# Sheet1.net
KiCad netlist of a schematic drawn in Altium Designer
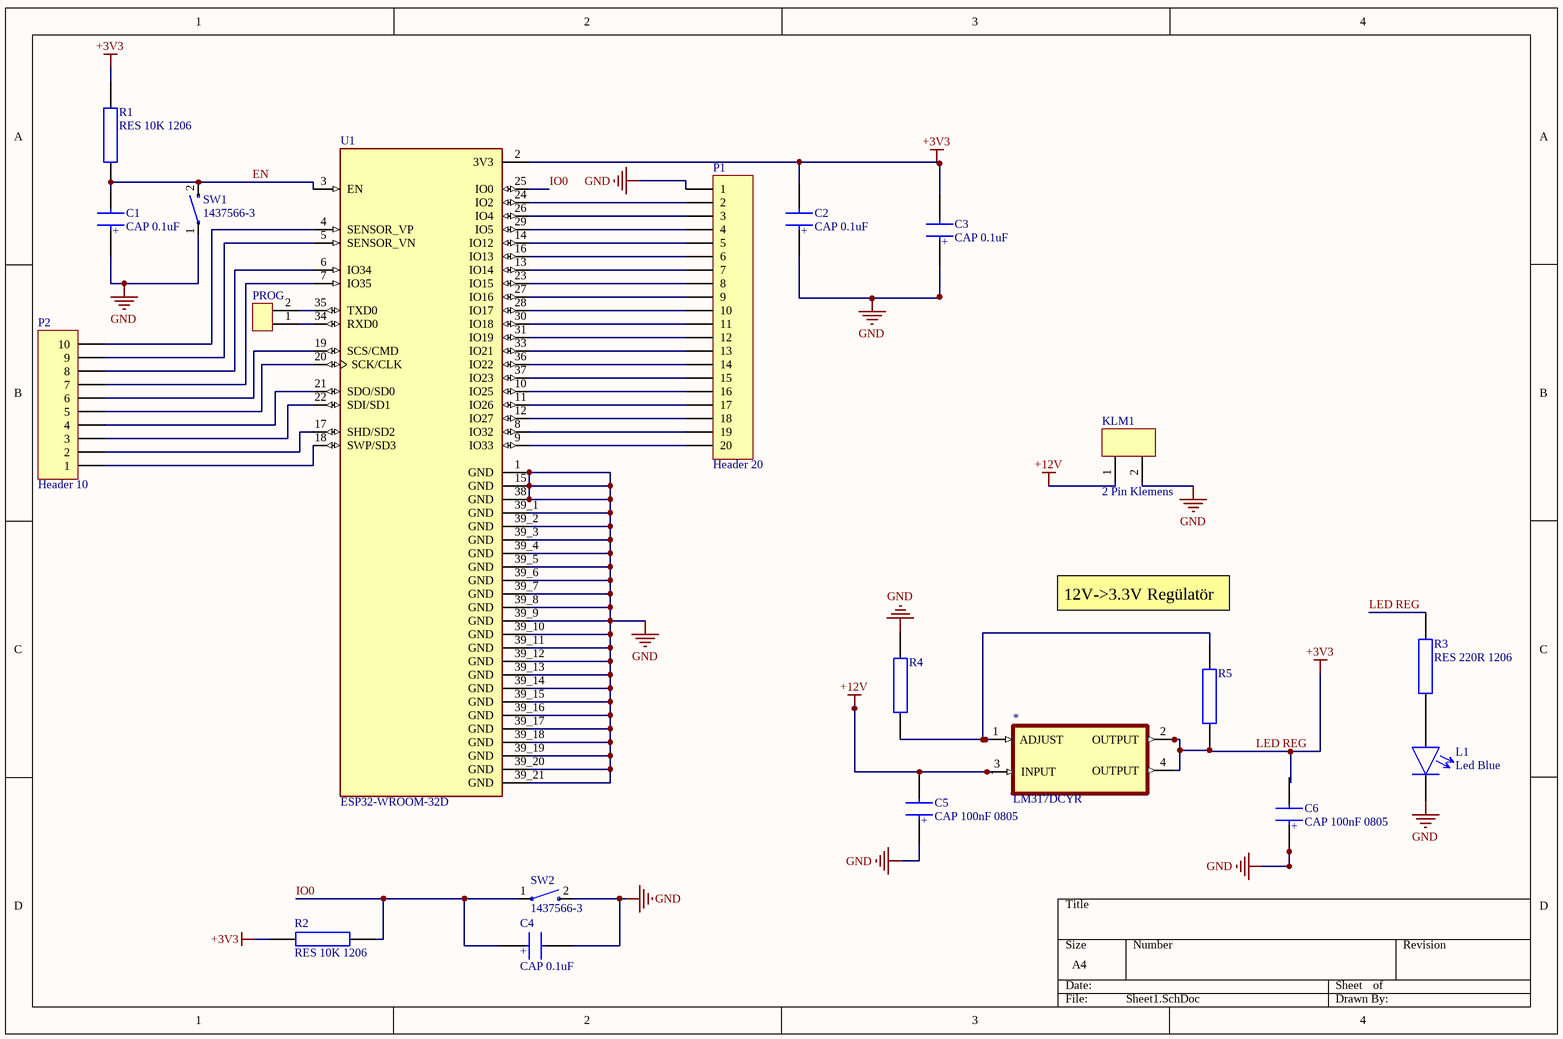
[diagram p0: Sheet1.SchDoc]

(export (version "E")
  (design (tool "Eeschema 10.0.6"))
  (components
    (comp (ref "*")
      (value "LM317DCYR")
      (footprint "SOT230P700X180-4N")
      (libsource (lib "Schlib") (part "LM317DCYR"))
    )
    (comp (ref "C1")
      (value "CAP 0.1uF")
      (footprint "CAP_805")
      (description "0805 smd")
      (libsource (lib "Udemy_Schlib1") (part "CAP 1uF"))
    )
    (comp (ref "C2")
      (value "CAP 0.1uF")
      (footprint "CAP_805")
      (description "0805 smd")
      (libsource (lib "Udemy_Schlib1") (part "CAP 1uF"))
    )
    (comp (ref "C3")
      (value "CAP 0.1uF")
      (footprint "CAP_805")
      (description "0805 smd")
      (libsource (lib "Udemy_Schlib1") (part "CAP 1uF"))
    )
    (comp (ref "C4")
      (value "CAP 0.1uF")
      (footprint "CAP_805")
      (description "0805 smd")
      (libsource (lib "Udemy_Schlib1") (part "CAP 1uF"))
    )
    (comp (ref "C5")
      (value "CAP 100nF 0805")
      (footprint "CAP_805")
      (description "0805 smd")
      (libsource (lib "Udemy_Schlib1") (part "CAP 100nF 0805"))
    )
    (comp (ref "C6")
      (value "CAP 100nF 0805")
      (footprint "CAP_805")
      (description "0805 smd")
      (libsource (lib "Udemy_Schlib1") (part "CAP 100nF 0805"))
    )
    (comp (ref "KLM1")
      (value "2 Pin Klemens")
      (footprint "5.08mm-2 pin")
      (description "5.08mm 2 pin klemens")
      (libsource (lib "Udemy_Schlib1") (part "2 Pin Klemens"))
    )
    (comp (ref "L1")
      (value "Led Blue")
      (footprint "Led 1206")
      (libsource (lib "Udemy_Schlib1") (part "Led Blue"))
    )
    (comp (ref "P1")
      (value "Header 20")
      (footprint "HDR1X20")
      (description "Header, 20-Pin")
      (fields (field (name "PUBLISHER") "Altium Limited"))
      (libsource (lib "Miscellaneous Connectors") (part "Header 20"))
    )
    (comp (ref "P2")
      (value "Header 10")
      (footprint "HDR1X10")
      (description "Header, 10-Pin")
      (fields (field (name "PUBLISHER") "Altium Limited"))
      (libsource (lib "Miscellaneous Connectors") (part "Header 10"))
    )
    (comp (ref "PROG")
      (value "2 Pin Jst Konnektör")
      (footprint "2 pin konnektor")
      (description "2.50 mm 2 pin jst")
      (libsource (lib "Udemy_Schlib1") (part "2 Pin Jst Konnektör"))
    )
    (comp (ref "R1")
      (value "RES 10K 1206")
      (footprint "RES_1206")
      (libsource (lib "Udemy_Schlib1") (part "RES 10K 1206"))
    )
    (comp (ref "R2")
      (value "RES 10K 1206")
      (footprint "RES_1206")
      (libsource (lib "Udemy_Schlib1") (part "RES 10K 1206"))
    )
    (comp (ref "R3")
      (value "RES 220R 1206")
      (footprint "RES_1206")
      (libsource (lib "Udemy_Schlib1") (part "RES 220R 1206"))
    )
    (comp (ref "R4")
      (value "RES 470R 1206")
      (footprint "RES_1206")
      (libsource (lib "Udemy_Schlib1") (part "RES 470R 1206"))
    )
    (comp (ref "R5")
      (value "RES 470R 1206")
      (footprint "RES_1206")
      (libsource (lib "Udemy_Schlib1") (part "RES 470R 1206"))
    )
    (comp (ref "SW1")
      (value "1437566-3")
      (footprint "SW_1437566-3")
      (description "Switch Tactile OFF (ON) SPST Rectangular Button Gull Wing 0.05A 12VDC SMD Loose Piece")
      (libsource (lib "Schlib") (part "1437566-3"))
    )
    (comp (ref "SW2")
      (value "1437566-3")
      (footprint "SW_1437566-3")
      (description "Switch Tactile OFF (ON) SPST Rectangular Button Gull Wing 0.05A 12VDC SMD Loose Piece")
      (libsource (lib "Schlib") (part "1437566-3"))
    )
    (comp (ref "U1")
      (value "ESP32-WROOM-32D")
      (footprint "MODULE_ESP32-WROOM-32D")
      (fields (field (name "MF") "Espressif Systems"))
      (libsource (lib "Schlib") (part "ESP32-WROOM-32D"))
    )
  )
  (nets
    (net (code "1") (name "+3V3") (class "Default")
      (node (ref "*") (pin "2") (pinfunction "OUTPUT_2") (pintype "output"))
      (node (ref "*") (pin "4") (pinfunction "OUTPUT_4") (pintype "output"))
      (node (ref "C2") (pin "2") (pinfunction "2_2") (pintype "passive"))
      (node (ref "C3") (pin "2") (pinfunction "2_2") (pintype "passive"))
      (node (ref "R1") (pin "2") (pintype "passive"))
      (node (ref "R2") (pin "2") (pintype "passive"))
      (node (ref "R3") (pin "2") (pintype "passive"))
      (node (ref "R5") (pin "1") (pintype "passive"))
      (node (ref "U1") (pin "2") (pinfunction "3V3_2") (pintype "power_in"))
    )
    (net (code "2") (name "+12V") (class "Default")
      (node (ref "*") (pin "3") (pinfunction "INPUT_3") (pintype "input"))
      (node (ref "C5") (pin "2") (pinfunction "2_2") (pintype "passive"))
      (node (ref "KLM1") (pin "1") (pintype "passive"))
    )
    (net (code "3") (name "/EN") (class "Default")
      (node (ref "C1") (pin "2") (pinfunction "2_2") (pintype "passive"))
      (node (ref "R1") (pin "1") (pintype "passive"))
      (node (ref "SW1") (pin "2") (pinfunction "2_2") (pintype "passive"))
      (node (ref "U1") (pin "3") (pinfunction "EN_3") (pintype "input"))
    )
    (net (code "4") (name "/IO0") (class "Default")
      (node (ref "C4") (pin "1") (pinfunction "1_1") (pintype "passive"))
      (node (ref "R2") (pin "1") (pintype "passive"))
      (node (ref "SW2") (pin "1") (pinfunction "1_1") (pintype "passive"))
      (node (ref "U1") (pin "25") (pinfunction "IO0_25") (pintype "bidirectional"))
    )
    (net (code "5") (name "GND") (class "Default")
      (node (ref "C1") (pin "1") (pinfunction "1_1") (pintype "passive"))
      (node (ref "C2") (pin "1") (pinfunction "1_1") (pintype "passive"))
      (node (ref "C3") (pin "1") (pinfunction "1_1") (pintype "passive"))
      (node (ref "C4") (pin "2") (pinfunction "2_2") (pintype "passive"))
      (node (ref "C5") (pin "1") (pinfunction "1_1") (pintype "passive"))
      (node (ref "C6") (pin "1") (pinfunction "1_1") (pintype "passive"))
      (node (ref "KLM1") (pin "2") (pintype "passive"))
      (node (ref "L1") (pin "2") (pintype "passive"))
      (node (ref "P1") (pin "1") (pinfunction "1_1") (pintype "passive"))
      (node (ref "R4") (pin "2") (pintype "passive"))
      (node (ref "SW1") (pin "1") (pinfunction "1_1") (pintype "passive"))
      (node (ref "SW2") (pin "2") (pinfunction "2_2") (pintype "passive"))
      (node (ref "U1") (pin "1") (pinfunction "GND_1") (pintype "power_in"))
      (node (ref "U1") (pin "15") (pinfunction "GND_15") (pintype "power_in"))
      (node (ref "U1") (pin "38") (pinfunction "GND_38") (pintype "power_in"))
      (node (ref "U1") (pin "39_1") (pinfunction "GND_39_1") (pintype "power_in"))
      (node (ref "U1") (pin "39_10") (pinfunction "GND_39_10") (pintype "power_in"))
      (node (ref "U1") (pin "39_11") (pinfunction "GND_39_11") (pintype "power_in"))
      (node (ref "U1") (pin "39_12") (pinfunction "GND_39_12") (pintype "power_in"))
      (node (ref "U1") (pin "39_13") (pinfunction "GND_39_13") (pintype "power_in"))
      (node (ref "U1") (pin "39_14") (pinfunction "GND_39_14") (pintype "power_in"))
      (node (ref "U1") (pin "39_15") (pinfunction "GND_39_15") (pintype "power_in"))
      (node (ref "U1") (pin "39_16") (pinfunction "GND_39_16") (pintype "power_in"))
      (node (ref "U1") (pin "39_17") (pinfunction "GND_39_17") (pintype "power_in"))
      (node (ref "U1") (pin "39_18") (pinfunction "GND_39_18") (pintype "power_in"))
      (node (ref "U1") (pin "39_19") (pinfunction "GND_39_19") (pintype "power_in"))
      (node (ref "U1") (pin "39_2") (pinfunction "GND_39_2") (pintype "power_in"))
      (node (ref "U1") (pin "39_20") (pinfunction "GND_39_20") (pintype "power_in"))
      (node (ref "U1") (pin "39_21") (pinfunction "GND_39_21") (pintype "power_in"))
      (node (ref "U1") (pin "39_3") (pinfunction "GND_39_3") (pintype "power_in"))
      (node (ref "U1") (pin "39_4") (pinfunction "GND_39_4") (pintype "power_in"))
      (node (ref "U1") (pin "39_5") (pinfunction "GND_39_5") (pintype "power_in"))
      (node (ref "U1") (pin "39_6") (pinfunction "GND_39_6") (pintype "power_in"))
      (node (ref "U1") (pin "39_7") (pinfunction "GND_39_7") (pintype "power_in"))
      (node (ref "U1") (pin "39_8") (pinfunction "GND_39_8") (pintype "power_in"))
      (node (ref "U1") (pin "39_9") (pinfunction "GND_39_9") (pintype "power_in"))
    )
    (net (code "6") (name "Net-(*-ADJUST)") (class "Default")
      (node (ref "*") (pin "1") (pinfunction "ADJUST_1") (pintype "input"))
      (node (ref "R4") (pin "1") (pintype "passive"))
      (node (ref "R5") (pin "2") (pintype "passive"))
    )
    (net (code "7") (name "Net-(L1-Pad1)") (class "Default")
      (node (ref "L1") (pin "1") (pintype "passive"))
      (node (ref "R3") (pin "1") (pintype "passive"))
    )
    (net (code "8") (name "Net-(U1-IO2)") (class "Default")
      (node (ref "P1") (pin "2") (pinfunction "2_2") (pintype "passive"))
      (node (ref "U1") (pin "24") (pinfunction "IO2_24") (pintype "bidirectional"))
    )
    (net (code "9") (name "Net-(U1-IO4)") (class "Default")
      (node (ref "P1") (pin "3") (pinfunction "3_3") (pintype "passive"))
      (node (ref "U1") (pin "26") (pinfunction "IO4_26") (pintype "bidirectional"))
    )
    (net (code "10") (name "Net-(U1-IO5)") (class "Default")
      (node (ref "P1") (pin "4") (pinfunction "4_4") (pintype "passive"))
      (node (ref "U1") (pin "29") (pinfunction "IO5_29") (pintype "bidirectional"))
    )
    (net (code "11") (name "Net-(U1-IO12)") (class "Default")
      (node (ref "P1") (pin "5") (pinfunction "5_5") (pintype "passive"))
      (node (ref "U1") (pin "14") (pinfunction "IO12_14") (pintype "bidirectional"))
    )
    (net (code "12") (name "Net-(U1-IO13)") (class "Default")
      (node (ref "P1") (pin "6") (pinfunction "6_6") (pintype "passive"))
      (node (ref "U1") (pin "16") (pinfunction "IO13_16") (pintype "bidirectional"))
    )
    (net (code "13") (name "Net-(U1-IO14)") (class "Default")
      (node (ref "P1") (pin "7") (pinfunction "7_7") (pintype "passive"))
      (node (ref "U1") (pin "13") (pinfunction "IO14_13") (pintype "bidirectional"))
    )
    (net (code "14") (name "Net-(U1-IO15)") (class "Default")
      (node (ref "P1") (pin "8") (pinfunction "8_8") (pintype "passive"))
      (node (ref "U1") (pin "23") (pinfunction "IO15_23") (pintype "bidirectional"))
    )
    (net (code "15") (name "Net-(U1-IO16)") (class "Default")
      (node (ref "P1") (pin "9") (pinfunction "9_9") (pintype "passive"))
      (node (ref "U1") (pin "27") (pinfunction "IO16_27") (pintype "bidirectional"))
    )
    (net (code "16") (name "Net-(U1-IO17)") (class "Default")
      (node (ref "P1") (pin "10") (pinfunction "10_10") (pintype "passive"))
      (node (ref "U1") (pin "28") (pinfunction "IO17_28") (pintype "bidirectional"))
    )
    (net (code "17") (name "Net-(U1-IO18)") (class "Default")
      (node (ref "P1") (pin "11") (pinfunction "11_11") (pintype "passive"))
      (node (ref "U1") (pin "30") (pinfunction "IO18_30") (pintype "bidirectional"))
    )
    (net (code "18") (name "Net-(U1-IO19)") (class "Default")
      (node (ref "P1") (pin "12") (pinfunction "12_12") (pintype "passive"))
      (node (ref "U1") (pin "31") (pinfunction "IO19_31") (pintype "bidirectional"))
    )
    (net (code "19") (name "Net-(U1-IO21)") (class "Default")
      (node (ref "P1") (pin "13") (pinfunction "13_13") (pintype "passive"))
      (node (ref "U1") (pin "33") (pinfunction "IO21_33") (pintype "bidirectional"))
    )
    (net (code "20") (name "Net-(U1-IO22)") (class "Default")
      (node (ref "P1") (pin "14") (pinfunction "14_14") (pintype "passive"))
      (node (ref "U1") (pin "36") (pinfunction "IO22_36") (pintype "bidirectional"))
    )
    (net (code "21") (name "Net-(U1-IO23)") (class "Default")
      (node (ref "P1") (pin "15") (pinfunction "15_15") (pintype "passive"))
      (node (ref "U1") (pin "37") (pinfunction "IO23_37") (pintype "bidirectional"))
    )
    (net (code "22") (name "Net-(U1-IO25)") (class "Default")
      (node (ref "P1") (pin "16") (pinfunction "16_16") (pintype "passive"))
      (node (ref "U1") (pin "10") (pinfunction "IO25_10") (pintype "bidirectional"))
    )
    (net (code "23") (name "Net-(U1-IO26)") (class "Default")
      (node (ref "P1") (pin "17") (pinfunction "17_17") (pintype "passive"))
      (node (ref "U1") (pin "11") (pinfunction "IO26_11") (pintype "bidirectional"))
    )
    (net (code "24") (name "Net-(U1-IO27)") (class "Default")
      (node (ref "P1") (pin "18") (pinfunction "18_18") (pintype "passive"))
      (node (ref "U1") (pin "12") (pinfunction "IO27_12") (pintype "bidirectional"))
    )
    (net (code "25") (name "Net-(U1-IO32)") (class "Default")
      (node (ref "P1") (pin "19") (pinfunction "19_19") (pintype "passive"))
      (node (ref "U1") (pin "8") (pinfunction "IO32_8") (pintype "bidirectional"))
    )
    (net (code "26") (name "Net-(U1-IO33)") (class "Default")
      (node (ref "P1") (pin "20") (pinfunction "20_20") (pintype "passive"))
      (node (ref "U1") (pin "9") (pinfunction "IO33_9") (pintype "bidirectional"))
    )
    (net (code "27") (name "Net-(U1-IO34)") (class "Default")
      (node (ref "P2") (pin "8") (pinfunction "8_8") (pintype "passive"))
      (node (ref "U1") (pin "6") (pinfunction "IO34_6") (pintype "input"))
    )
    (net (code "28") (name "Net-(U1-IO35)") (class "Default")
      (node (ref "P2") (pin "7") (pinfunction "7_7") (pintype "passive"))
      (node (ref "U1") (pin "7") (pinfunction "IO35_7") (pintype "input"))
    )
    (net (code "29") (name "Net-(U1-RXD0)") (class "Default")
      (node (ref "PROG") (pin "1") (pintype "passive"))
      (node (ref "U1") (pin "34") (pinfunction "RXD0_34") (pintype "bidirectional"))
    )
    (net (code "30") (name "Net-(U1-SCK{slash}CLK)") (class "Default")
      (node (ref "P2") (pin "5") (pinfunction "5_5") (pintype "passive"))
      (node (ref "U1") (pin "20") (pinfunction "SCK/CLK_20") (pintype "bidirectional"))
    )
    (net (code "31") (name "Net-(U1-SCS{slash}CMD)") (class "Default")
      (node (ref "P2") (pin "6") (pinfunction "6_6") (pintype "passive"))
      (node (ref "U1") (pin "19") (pinfunction "SCS/CMD_19") (pintype "bidirectional"))
    )
    (net (code "32") (name "Net-(U1-SDI{slash}SD1)") (class "Default")
      (node (ref "P2") (pin "3") (pinfunction "3_3") (pintype "passive"))
      (node (ref "U1") (pin "22") (pinfunction "SDI/SD1_22") (pintype "bidirectional"))
    )
    (net (code "33") (name "Net-(U1-SDO{slash}SD0)") (class "Default")
      (node (ref "P2") (pin "4") (pinfunction "4_4") (pintype "passive"))
      (node (ref "U1") (pin "21") (pinfunction "SDO/SD0_21") (pintype "bidirectional"))
    )
    (net (code "34") (name "Net-(U1-SENSOR_VN)") (class "Default")
      (node (ref "P2") (pin "9") (pinfunction "9_9") (pintype "passive"))
      (node (ref "U1") (pin "5") (pinfunction "SENSOR_VN_5") (pintype "input"))
    )
    (net (code "35") (name "Net-(U1-SENSOR_VP)") (class "Default")
      (node (ref "P2") (pin "10") (pinfunction "10_10") (pintype "passive"))
      (node (ref "U1") (pin "4") (pinfunction "SENSOR_VP_4") (pintype "input"))
    )
    (net (code "36") (name "Net-(U1-SHD{slash}SD2)") (class "Default")
      (node (ref "P2") (pin "2") (pinfunction "2_2") (pintype "passive"))
      (node (ref "U1") (pin "17") (pinfunction "SHD/SD2_17") (pintype "bidirectional"))
    )
    (net (code "37") (name "Net-(U1-SWP{slash}SD3)") (class "Default")
      (node (ref "P2") (pin "1") (pinfunction "1_1") (pintype "passive"))
      (node (ref "U1") (pin "18") (pinfunction "SWP/SD3_18") (pintype "bidirectional"))
    )
    (net (code "38") (name "Net-(U1-TXD0)") (class "Default")
      (node (ref "PROG") (pin "2") (pintype "passive"))
      (node (ref "U1") (pin "35") (pinfunction "TXD0_35") (pintype "bidirectional"))
    )
    (net (code "39") (name "unconnected-(C6-Pad2)") (class "Default")
      (node (ref "C6") (pin "2") (pinfunction "2_2") (pintype "passive"))
    )
  )
)
